# JFETSOT23_DCBias.net
KiCad netlist of a schematic drawn in Altium Designer
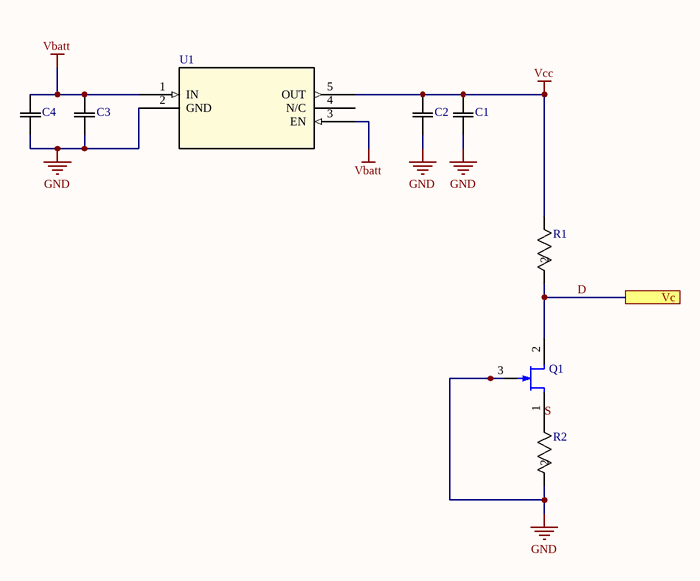
[diagram p0: JFETSOT23_DCBias.SchDoc]

(export (version "E")
  (design (tool "Eeschema 10.0.6"))
  (components
    (comp (ref "C1")
      (value "~")
      (footprint "YAG_CC0402")
      (description "No Description Available")
      (fields
        (field (name "MANUFACTURER_PART_NUMBER") "CC0402KRX7R9BB103")
        (field (name "COPYRIGHT") "Copyright (C) 2018 Accelerated Designs. All rights reserved")
      )
      (libsource (lib "0402Capacitor_Yageo") (part "CC0402KRX7R9BB10"))
    )
    (comp (ref "C2")
      (value "~")
      (footprint "YAG_CC0402")
      (description "No Description Available")
      (fields
        (field (name "MANUFACTURER_PART_NUMBER") "CC0402KRX7R9BB103")
        (field (name "COPYRIGHT") "Copyright (C) 2018 Accelerated Designs. All rights reserved")
      )
      (libsource (lib "0402Capacitor_Yageo") (part "CC0402KRX7R9BB10"))
    )
    (comp (ref "C3")
      (value "~")
      (footprint "YAG_CC0402")
      (description "No Description Available")
      (fields
        (field (name "MANUFACTURER_PART_NUMBER") "CC0402KRX7R9BB103")
        (field (name "COPYRIGHT") "Copyright (C) 2018 Accelerated Designs. All rights reserved")
      )
      (libsource (lib "0402Capacitor_Yageo") (part "CC0402KRX7R9BB10"))
    )
    (comp (ref "C4")
      (value "~")
      (footprint "YAG_CC0402")
      (description "No Description Available")
      (fields
        (field (name "MANUFACTURER_PART_NUMBER") "CC0402KRX7R9BB103")
        (field (name "COPYRIGHT") "Copyright (C) 2018 Accelerated Designs. All rights reserved")
      )
      (libsource (lib "0402Capacitor_Yageo") (part "CC0402KRX7R9BB10"))
    )
    (comp (ref "Q1")
      (value "~")
      (footprint "ONSC-CP-3-318AN_A_V")
      (description "N-Channel JFET, 15 V, 10 to 20 mA, 38 mS, 3-Pin CP, Pb-Free, Tape and Reel")
      (fields (field (name "MANUFACTURER") "On Semiconductor") (field (name "PARTNUMBER") "2SK2394-6-TB-E"))
      (libsource (lib "ON Semi JFETs") (part "2SK2394-6-TB-E"))
    )
    (comp (ref "R1")
      (value "~")
      (footprint "RC0402N")
      (description "No Description Available")
      (fields
        (field (name "MANUFACTURER_PART_NUMBER") "RC0402JR-070RL")
        (field (name "COPYRIGHT") "Copyright (C) 2018 Accelerated Designs. All rights reserved")
      )
      (libsource (lib "Resistor0402Yageo") (part "RC0402JR-070RL"))
    )
    (comp (ref "R2")
      (value "~")
      (footprint "RC0402N")
      (description "No Description Available")
      (fields
        (field (name "MANUFACTURER_PART_NUMBER") "RC0402JR-070RL")
        (field (name "COPYRIGHT") "Copyright (C) 2018 Accelerated Designs. All rights reserved")
      )
      (libsource (lib "Resistor0402Yageo") (part "RC0402JR-070RL"))
    )
    (comp (ref "U1")
      (value "~")
      (footprint "DBV5")
      (description "No Description Available")
      (fields
        (field (name "MANUFACTURER_PART_NUMBER") "LP5907MFX-3.3/NOPB")
        (field (name "COPYRIGHT") "Copyright (C) 2018 Accelerated Designs. All rights reserved")
      )
      (libsource (lib "TI_LDO_3V3_SOT325") (part "LP5907MFX-3.3/NO"))
    )
  )
  (nets
    (net (code "1") (name "/D") (class "Default")
      (node (ref "Q1") (pin "2") (pinfunction "D_2") (pintype "passive"))
      (node (ref "R1") (pin "2") (pinfunction "2_2") (pintype "passive"))
    )
    (net (code "2") (name "/S") (class "Default")
      (node (ref "Q1") (pin "1") (pinfunction "S_1") (pintype "passive"))
      (node (ref "R2") (pin "1") (pinfunction "1_1") (pintype "passive"))
    )
    (net (code "3") (name "GND") (class "Default")
      (node (ref "C1") (pin "1") (pinfunction "1_1") (pintype "passive"))
      (node (ref "C2") (pin "1") (pinfunction "1_1") (pintype "passive"))
      (node (ref "C3") (pin "1") (pinfunction "1_1") (pintype "passive"))
      (node (ref "C4") (pin "1") (pinfunction "1_1") (pintype "passive"))
      (node (ref "Q1") (pin "3") (pinfunction "G_3") (pintype "passive"))
      (node (ref "R2") (pin "2") (pinfunction "2_2") (pintype "passive"))
      (node (ref "U1") (pin "2") (pinfunction "GND_2") (pintype "power_in"))
    )
    (net (code "4") (name "Vbatt") (class "Default")
      (node (ref "C3") (pin "2") (pinfunction "2_2") (pintype "passive"))
      (node (ref "C4") (pin "2") (pinfunction "2_2") (pintype "passive"))
      (node (ref "U1") (pin "1") (pinfunction "IN_1") (pintype "input"))
      (node (ref "U1") (pin "3") (pinfunction "EN_3") (pintype "input"))
    )
    (net (code "5") (name "Vcc") (class "Default")
      (node (ref "C1") (pin "2") (pinfunction "2_2") (pintype "passive"))
      (node (ref "C2") (pin "2") (pinfunction "2_2") (pintype "passive"))
      (node (ref "R1") (pin "1") (pinfunction "1_1") (pintype "passive"))
      (node (ref "U1") (pin "5") (pinfunction "OUT_5") (pintype "output"))
    )
    (net (code "6") (name "unconnected-(U1-N{slash}C-Pad4)") (class "Default")
      (node (ref "U1") (pin "4") (pinfunction "N/C_4") (pintype "passive"))
    )
  )
)
